# 1_Power_Management_schdoc.net
KiCad netlist of a schematic drawn in Altium Designer
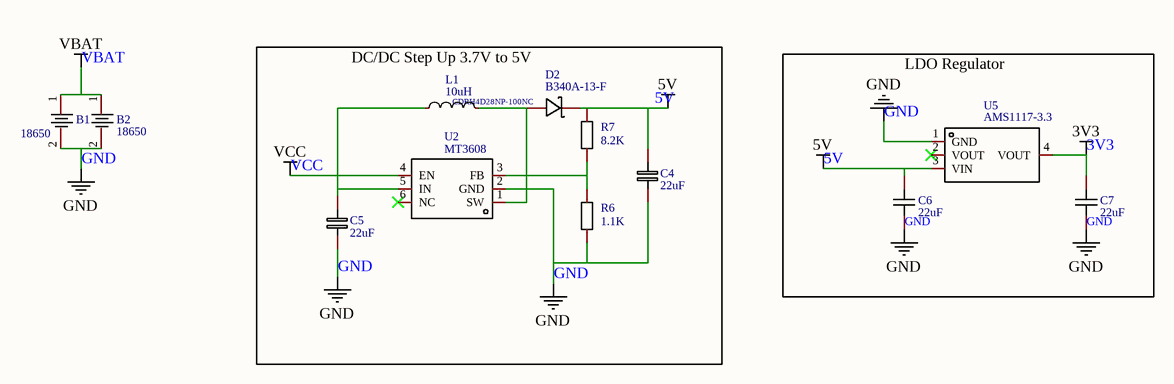
[diagram p0: 1_Power Management.schdoc.schdoc]

(export (version "E")
  (design (tool "Eeschema 10.0.6"))
  (components
    (comp (ref "B1")
      (value "18650")
      (fields
        (field (name "NAME") "18650")
        (field (name "MANUFACTURER") "Q&amp;J")
        (field (name "MANUFACTURER PART") "CR1220-2")
      )
      (libsource (lib "altium-import") (part "root_3_CR1220-2_"))
    )
    (comp (ref "B2")
      (value "18650")
      (fields
        (field (name "NAME") "18650")
        (field (name "MANUFACTURER") "Q&amp;J")
        (field (name "MANUFACTURER PART") "CR1220-2")
      )
      (libsource (lib "altium-import") (part "root_3_CR1220-2_"))
    )
    (comp (ref "C4")
      (value "22uF")
      (fields
        (field (name "NAME") "22uF")
        (field (name "MANUFACTURER") "FH(风华)")
        (field (name "MANUFACTURER PART") "1206X226M250NT")
      )
      (libsource (lib "") (part "root_1_1206X226M250NT__1"))
    )
    (comp (ref "C5")
      (value "22uF")
      (fields
        (field (name "NAME") "22uF")
        (field (name "MANUFACTURER") "FH(风华)")
        (field (name "MANUFACTURER PART") "1206X226M250NT")
      )
      (libsource (lib "") (part "root_1_1206X226M250NT__1"))
    )
    (comp (ref "C6")
      (value "22uF")
      (fields
        (field (name "NAME") "22uF")
        (field (name "MANUFACTURER") "FH(风华)")
        (field (name "MANUFACTURER PART") "1206X226M250NT")
      )
      (libsource (lib "altium-import") (part "root_1_1206X226M250NT_"))
    )
    (comp (ref "C7")
      (value "22uF")
      (fields
        (field (name "NAME") "22uF")
        (field (name "MANUFACTURER") "FH(风华)")
        (field (name "MANUFACTURER PART") "1206X226M250NT")
      )
      (libsource (lib "altium-import") (part "root_1_1206X226M250NT_"))
    )
    (comp (ref "D2")
      (value "B340A-13-F")
      (description "Reverse Voltage (Vr):40V Average Rectified Current (Io):3A Forward Voltage (Vf@If):500mV@3A")
      (fields (field (name "NAME") "B340A-13-F") (field (name "MANUFACTURER") "DIODES(美台)"))
      (libsource (lib "altium-import") (part "root_2_B340A-13-F_"))
    )
    (comp (ref "L1")
      (value "10uH")
      (fields
        (field (name "NAME") "10uH")
        (field (name "DEVICE") "CDRH4D28NP-100NC")
        (field (name "MANUFACTURER") "Sumida(胜美达)")
        (field (name "MANUFACTURER PART") "CDRH4D28NP-100NC")
        (field (name "TOLERANCE") "±30%")
      )
      (libsource (lib "altium-import") (part "root_0_CDRH4D28NP-100NC_"))
    )
    (comp (ref "R6")
      (value "1.1K")
      (fields (field (name "NAME") "1.1K"))
      (libsource (lib "altium-import") (part "root_1_Res_0603_"))
    )
    (comp (ref "R7")
      (value "8.2K")
      (fields (field (name "NAME") "8.2K"))
      (libsource (lib "altium-import") (part "root_1_Res_0603_"))
    )
    (comp (ref "U2")
      (value "MT3608")
      (fields (field (name "NAME") "MT3608") (field (name "MANUFACTURER") "西安航天民芯"))
      (libsource (lib "altium-import") (part "root_2_MT3608_"))
    )
    (comp (ref "U5")
      (value "AMS1117-3.3")
      (fields (field (name "NAME") "AMS1117-3.3") (field (name "MANUFACTURER") "国芯佳品"))
      (libsource (lib "altium-import") (part "root_0_AMS1117-3.3_"))
    )
  )
  (nets
    (net (code "1") (name "3V3") (class "Default")
      (node (ref "C7") (pin "2") (pinfunction "2_2") (pintype "passive"))
      (node (ref "U5") (pin "4") (pinfunction "VOUT_4") (pintype "passive"))
    )
    (net (code "2") (name "5V") (class "Default")
      (node (ref "C4") (pin "2") (pinfunction "2_2") (pintype "passive"))
      (node (ref "C6") (pin "2") (pinfunction "2_2") (pintype "passive"))
      (node (ref "D2") (pin "1") (pinfunction "K_1") (pintype "passive"))
      (node (ref "R7") (pin "2") (pinfunction "2_2") (pintype "passive"))
      (node (ref "U5") (pin "3") (pinfunction "VIN_3") (pintype "passive"))
    )
    (net (code "3") (name "GND") (class "Default")
      (node (ref "B1") (pin "2") (pinfunction "2_2") (pintype "passive"))
      (node (ref "B2") (pin "2") (pinfunction "2_2") (pintype "passive"))
      (node (ref "C4") (pin "1") (pinfunction "1_1") (pintype "passive"))
      (node (ref "C5") (pin "1") (pinfunction "1_1") (pintype "passive"))
      (node (ref "C6") (pin "1") (pinfunction "1_1") (pintype "passive"))
      (node (ref "C7") (pin "1") (pinfunction "1_1") (pintype "passive"))
      (node (ref "R6") (pin "1") (pinfunction "1_1") (pintype "passive"))
      (node (ref "U2") (pin "2") (pinfunction "GND_2") (pintype "passive"))
      (node (ref "U5") (pin "1") (pinfunction "GND_1") (pintype "passive"))
    )
    (net (code "4") (name "Net-(D2-A)") (class "Default")
      (node (ref "D2") (pin "2") (pinfunction "A_2") (pintype "passive"))
      (node (ref "L1") (pin "2") (pinfunction "2_2") (pintype "passive"))
      (node (ref "U2") (pin "1") (pinfunction "SW_1") (pintype "passive"))
    )
    (net (code "5") (name "Net-(U2-FB)") (class "Default")
      (node (ref "R6") (pin "2") (pinfunction "2_2") (pintype "passive"))
      (node (ref "R7") (pin "1") (pinfunction "1_1") (pintype "passive"))
      (node (ref "U2") (pin "3") (pinfunction "FB_3") (pintype "passive"))
    )
    (net (code "6") (name "VBAT") (class "Default")
      (node (ref "B1") (pin "1") (pinfunction "1_1") (pintype "passive"))
      (node (ref "B2") (pin "1") (pinfunction "1_1") (pintype "passive"))
    )
    (net (code "7") (name "VCC") (class "Default")
      (node (ref "C5") (pin "2") (pinfunction "2_2") (pintype "passive"))
      (node (ref "L1") (pin "1") (pinfunction "1_1") (pintype "passive"))
      (node (ref "U2") (pin "4") (pinfunction "EN_4") (pintype "passive"))
      (node (ref "U2") (pin "5") (pinfunction "IN_5") (pintype "passive"))
    )
    (net (code "8") (name "unconnected-(U2-NC-Pad6)") (class "Default")
      (node (ref "U2") (pin "6") (pinfunction "NC_6") (pintype "passive+no_connect"))
    )
    (net (code "9") (name "unconnected-(U5-VOUT-Pad2)") (class "Default")
      (node (ref "U5") (pin "2") (pinfunction "VOUT_2") (pintype "passive+no_connect"))
    )
  )
)
